# PCB_Control.net
KiCad netlist of a schematic drawn in EAGLE
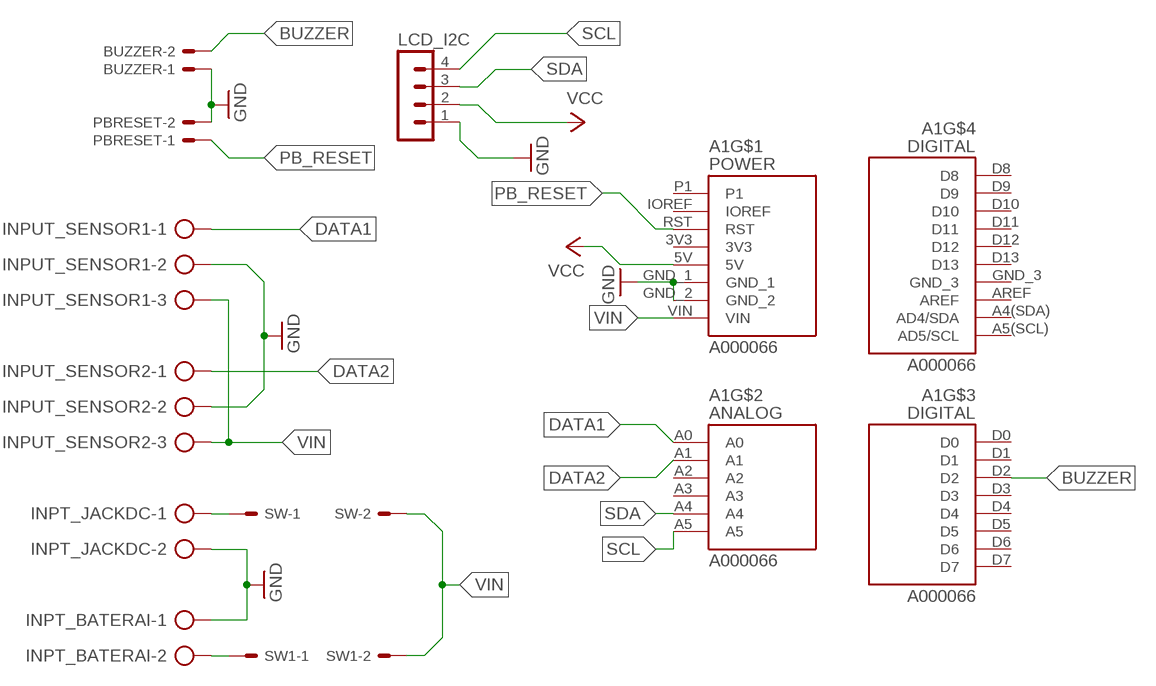
[diagram p0: schematic, sheet 1]

(export (version "E")
  (design (tool "Eeschema 10.0.6"))
  (components
    (comp (ref "A1")
      (value "A000066")
      (footprint "eagle-import:ARDUINO_A000066")
      (fields (field (name "MF") "Arduino") (field (name "MP") "ARDUINO UNO REV3 DEVELOPMENT BOARD"))
      (libsource (lib "eagle-import") (part "A000066"))
    )
    (comp (ref "BUZZER")
      (value "22-23-2021")
      (footprint "eagle-import:22-23-2021")
      (fields (field (name "MF") "MOLEX"))
      (libsource (lib "eagle-import") (part "22-23-2021"))
    )
    (comp (ref "INPT_BATERAI")
      (value "AK500/2")
      (footprint "eagle-import:AK500_2")
      (libsource (lib "eagle-import") (part "AK500/2"))
    )
    (comp (ref "INPT_JACKDC")
      (value "AK500/2")
      (footprint "eagle-import:AK500_2")
      (libsource (lib "eagle-import") (part "AK500/2"))
    )
    (comp (ref "INPUT_SENSOR1")
      (value "AK500/3")
      (footprint "eagle-import:AK500_3")
      (libsource (lib "eagle-import") (part "AK500/3"))
    )
    (comp (ref "INPUT_SENSOR2")
      (value "AK500/3")
      (footprint "eagle-import:AK500_3")
      (libsource (lib "eagle-import") (part "AK500/3"))
    )
    (comp (ref "LCD_I2C")
      (value "MA04-1")
      (footprint "eagle-import:MA04-1")
      (libsource (lib "eagle-import") (part "MA04-1"))
    )
    (comp (ref "PBRESET")
      (value "22-23-2021")
      (footprint "eagle-import:22-23-2021")
      (fields (field (name "MF") "MOLEX"))
      (libsource (lib "eagle-import") (part "22-23-2021"))
    )
    (comp (ref "SW")
      (value "22-23-2021")
      (footprint "eagle-import:22-23-2021")
      (fields (field (name "MF") "MOLEX"))
      (libsource (lib "eagle-import") (part "22-23-2021"))
    )
    (comp (ref "SW1")
      (value "22-23-2021")
      (footprint "eagle-import:22-23-2021")
      (fields (field (name "MF") "MOLEX"))
      (libsource (lib "eagle-import") (part "22-23-2021"))
    )
  )
  (nets
    (net (code "1") (name "/3V3") (class "Default")
      (node (ref "A1") (pin "3V3") (pinfunction "3V3_3V3") (pintype "power_in"))
    )
    (net (code "2") (name "/GND_3") (class "Default")
      (node (ref "A1") (pin "GND_3") (pinfunction "GND_3_GND_3") (pintype "power_in"))
    )
    (net (code "3") (name "BUZZER") (class "Default")
      (node (ref "A1") (pin "D2") (pinfunction "D2_D2") (pintype "bidirectional"))
      (node (ref "BUZZER") (pin "2") (pinfunction "S_2") (pintype "passive"))
    )
    (net (code "4") (name "DATA1") (class "Default")
      (node (ref "A1") (pin "A0") (pinfunction "A0_A0") (pintype "bidirectional"))
      (node (ref "INPUT_SENSOR1") (pin "1") (pinfunction "KL_1") (pintype "passive"))
    )
    (net (code "5") (name "DATA2") (class "Default")
      (node (ref "A1") (pin "A1") (pinfunction "A1_A1") (pintype "bidirectional"))
      (node (ref "INPUT_SENSOR2") (pin "1") (pinfunction "KL_1") (pintype "passive"))
    )
    (net (code "6") (name "GND") (class "Default")
      (node (ref "A1") (pin "GND_1") (pinfunction "GND_1_GND_1") (pintype "power_in"))
      (node (ref "A1") (pin "GND_2") (pinfunction "GND_2_GND_2") (pintype "power_in"))
      (node (ref "BUZZER") (pin "1") (pinfunction "S_1") (pintype "passive"))
      (node (ref "INPT_BATERAI") (pin "1") (pinfunction "KL_1") (pintype "passive"))
      (node (ref "INPT_JACKDC") (pin "2") (pinfunction "KL_2") (pintype "passive"))
      (node (ref "INPUT_SENSOR1") (pin "2") (pinfunction "KL_2") (pintype "passive"))
      (node (ref "INPUT_SENSOR2") (pin "2") (pinfunction "KL_2") (pintype "passive"))
      (node (ref "LCD_I2C") (pin "1") (pinfunction "1_1") (pintype "passive"))
      (node (ref "PBRESET") (pin "2") (pinfunction "S_2") (pintype "passive"))
    )
    (net (code "7") (name "Net-(INPT_BATERAIB-KL)") (class "Default")
      (node (ref "INPT_BATERAI") (pin "2") (pinfunction "KL_2") (pintype "passive"))
      (node (ref "SW1") (pin "1") (pinfunction "S_1") (pintype "passive"))
    )
    (net (code "8") (name "Net-(INPT_JACKDCA-KL)") (class "Default")
      (node (ref "INPT_JACKDC") (pin "1") (pinfunction "KL_1") (pintype "passive"))
      (node (ref "SW") (pin "1") (pinfunction "S_1") (pintype "passive"))
    )
    (net (code "9") (name "PB_RESET") (class "Default")
      (node (ref "A1") (pin "RST") (pinfunction "RST_RST") (pintype "bidirectional"))
      (node (ref "PBRESET") (pin "1") (pinfunction "S_1") (pintype "passive"))
    )
    (net (code "10") (name "SCL") (class "Default")
      (node (ref "A1") (pin "A5") (pinfunction "A5_A5") (pintype "bidirectional"))
      (node (ref "LCD_I2C") (pin "4") (pinfunction "4_4") (pintype "passive"))
    )
    (net (code "11") (name "SDA") (class "Default")
      (node (ref "A1") (pin "A4") (pinfunction "A4_A4") (pintype "bidirectional"))
      (node (ref "LCD_I2C") (pin "3") (pinfunction "3_3") (pintype "passive"))
    )
    (net (code "12") (name "VCC") (class "Default")
      (node (ref "A1") (pin "5V") (pinfunction "5V_5V") (pintype "power_in"))
      (node (ref "LCD_I2C") (pin "2") (pinfunction "2_2") (pintype "passive"))
    )
    (net (code "13") (name "VIN") (class "Default")
      (node (ref "A1") (pin "VIN") (pinfunction "VIN_VIN") (pintype "power_in"))
      (node (ref "INPUT_SENSOR1") (pin "3") (pinfunction "KL_3") (pintype "passive"))
      (node (ref "INPUT_SENSOR2") (pin "3") (pinfunction "KL_3") (pintype "passive"))
      (node (ref "SW") (pin "2") (pinfunction "S_2") (pintype "passive"))
      (node (ref "SW1") (pin "2") (pinfunction "S_2") (pintype "passive"))
    )
    (net (code "14") (name "unconnected-(A1-PadA2)") (class "Default")
      (node (ref "A1") (pin "A2") (pinfunction "A2_A2") (pintype "bidirectional"))
    )
    (net (code "15") (name "unconnected-(A1-PadA3)") (class "Default")
      (node (ref "A1") (pin "A3") (pinfunction "A3_A3") (pintype "bidirectional"))
    )
    (net (code "16") (name "unconnected-(A1-PadAREF)") (class "Default")
      (node (ref "A1") (pin "AREF") (pinfunction "AREF_AREF") (pintype "bidirectional"))
    )
    (net (code "17") (name "unconnected-(A1-PadD0)") (class "Default")
      (node (ref "A1") (pin "D0") (pinfunction "D0_D0") (pintype "bidirectional"))
    )
    (net (code "18") (name "unconnected-(A1-PadD1)") (class "Default")
      (node (ref "A1") (pin "D1") (pinfunction "D1_D1") (pintype "bidirectional"))
    )
    (net (code "19") (name "unconnected-(A1-PadD3)") (class "Default")
      (node (ref "A1") (pin "D3") (pinfunction "D3_D3") (pintype "bidirectional"))
    )
    (net (code "20") (name "unconnected-(A1-PadD4)") (class "Default")
      (node (ref "A1") (pin "D4") (pinfunction "D4_D4") (pintype "bidirectional"))
    )
    (net (code "21") (name "unconnected-(A1-PadD5)") (class "Default")
      (node (ref "A1") (pin "D5") (pinfunction "D5_D5") (pintype "bidirectional"))
    )
    (net (code "22") (name "unconnected-(A1-PadD6)") (class "Default")
      (node (ref "A1") (pin "D6") (pinfunction "D6_D6") (pintype "bidirectional"))
    )
    (net (code "23") (name "unconnected-(A1-PadD7)") (class "Default")
      (node (ref "A1") (pin "D7") (pinfunction "D7_D7") (pintype "bidirectional"))
    )
    (net (code "24") (name "unconnected-(A1-PadD8)") (class "Default")
      (node (ref "A1") (pin "D8") (pinfunction "D8_D8") (pintype "bidirectional"))
    )
    (net (code "25") (name "unconnected-(A1-PadD9)") (class "Default")
      (node (ref "A1") (pin "D9") (pinfunction "D9_D9") (pintype "bidirectional"))
    )
    (net (code "26") (name "unconnected-(A1-PadD10)") (class "Default")
      (node (ref "A1") (pin "D10") (pinfunction "D10_D10") (pintype "bidirectional"))
    )
    (net (code "27") (name "unconnected-(A1-PadD11)") (class "Default")
      (node (ref "A1") (pin "D11") (pinfunction "D11_D11") (pintype "bidirectional"))
    )
    (net (code "28") (name "unconnected-(A1-PadD12)") (class "Default")
      (node (ref "A1") (pin "D12") (pinfunction "D12_D12") (pintype "bidirectional"))
    )
    (net (code "29") (name "unconnected-(A1-PadD13)") (class "Default")
      (node (ref "A1") (pin "D13") (pinfunction "D13_D13") (pintype "bidirectional"))
    )
    (net (code "30") (name "unconnected-(A1-PadIOREF)") (class "Default")
      (node (ref "A1") (pin "IOREF") (pinfunction "IOREF_IOREF") (pintype "bidirectional"))
    )
    (net (code "31") (name "unconnected-(A1-PadP1)") (class "Default")
      (node (ref "A1") (pin "P1") (pinfunction "P1_P1") (pintype "bidirectional"))
    )
    (net (code "32") (name "unconnected-(A1D-AD4{slash}SDA-PadA4(SDA))") (class "Default")
      (node (ref "A1") (pin "A4(SDA)") (pinfunction "AD4/SDA_A4(SDA)") (pintype "bidirectional"))
    )
    (net (code "33") (name "unconnected-(A1D-AD5{slash}SCL-PadA5(SCL))") (class "Default")
      (node (ref "A1") (pin "A5(SCL)") (pinfunction "AD5/SCL_A5(SCL)") (pintype "bidirectional"))
    )
  )
)
